# LMD18200_4.net
KiCad netlist of a schematic drawn in EAGLE
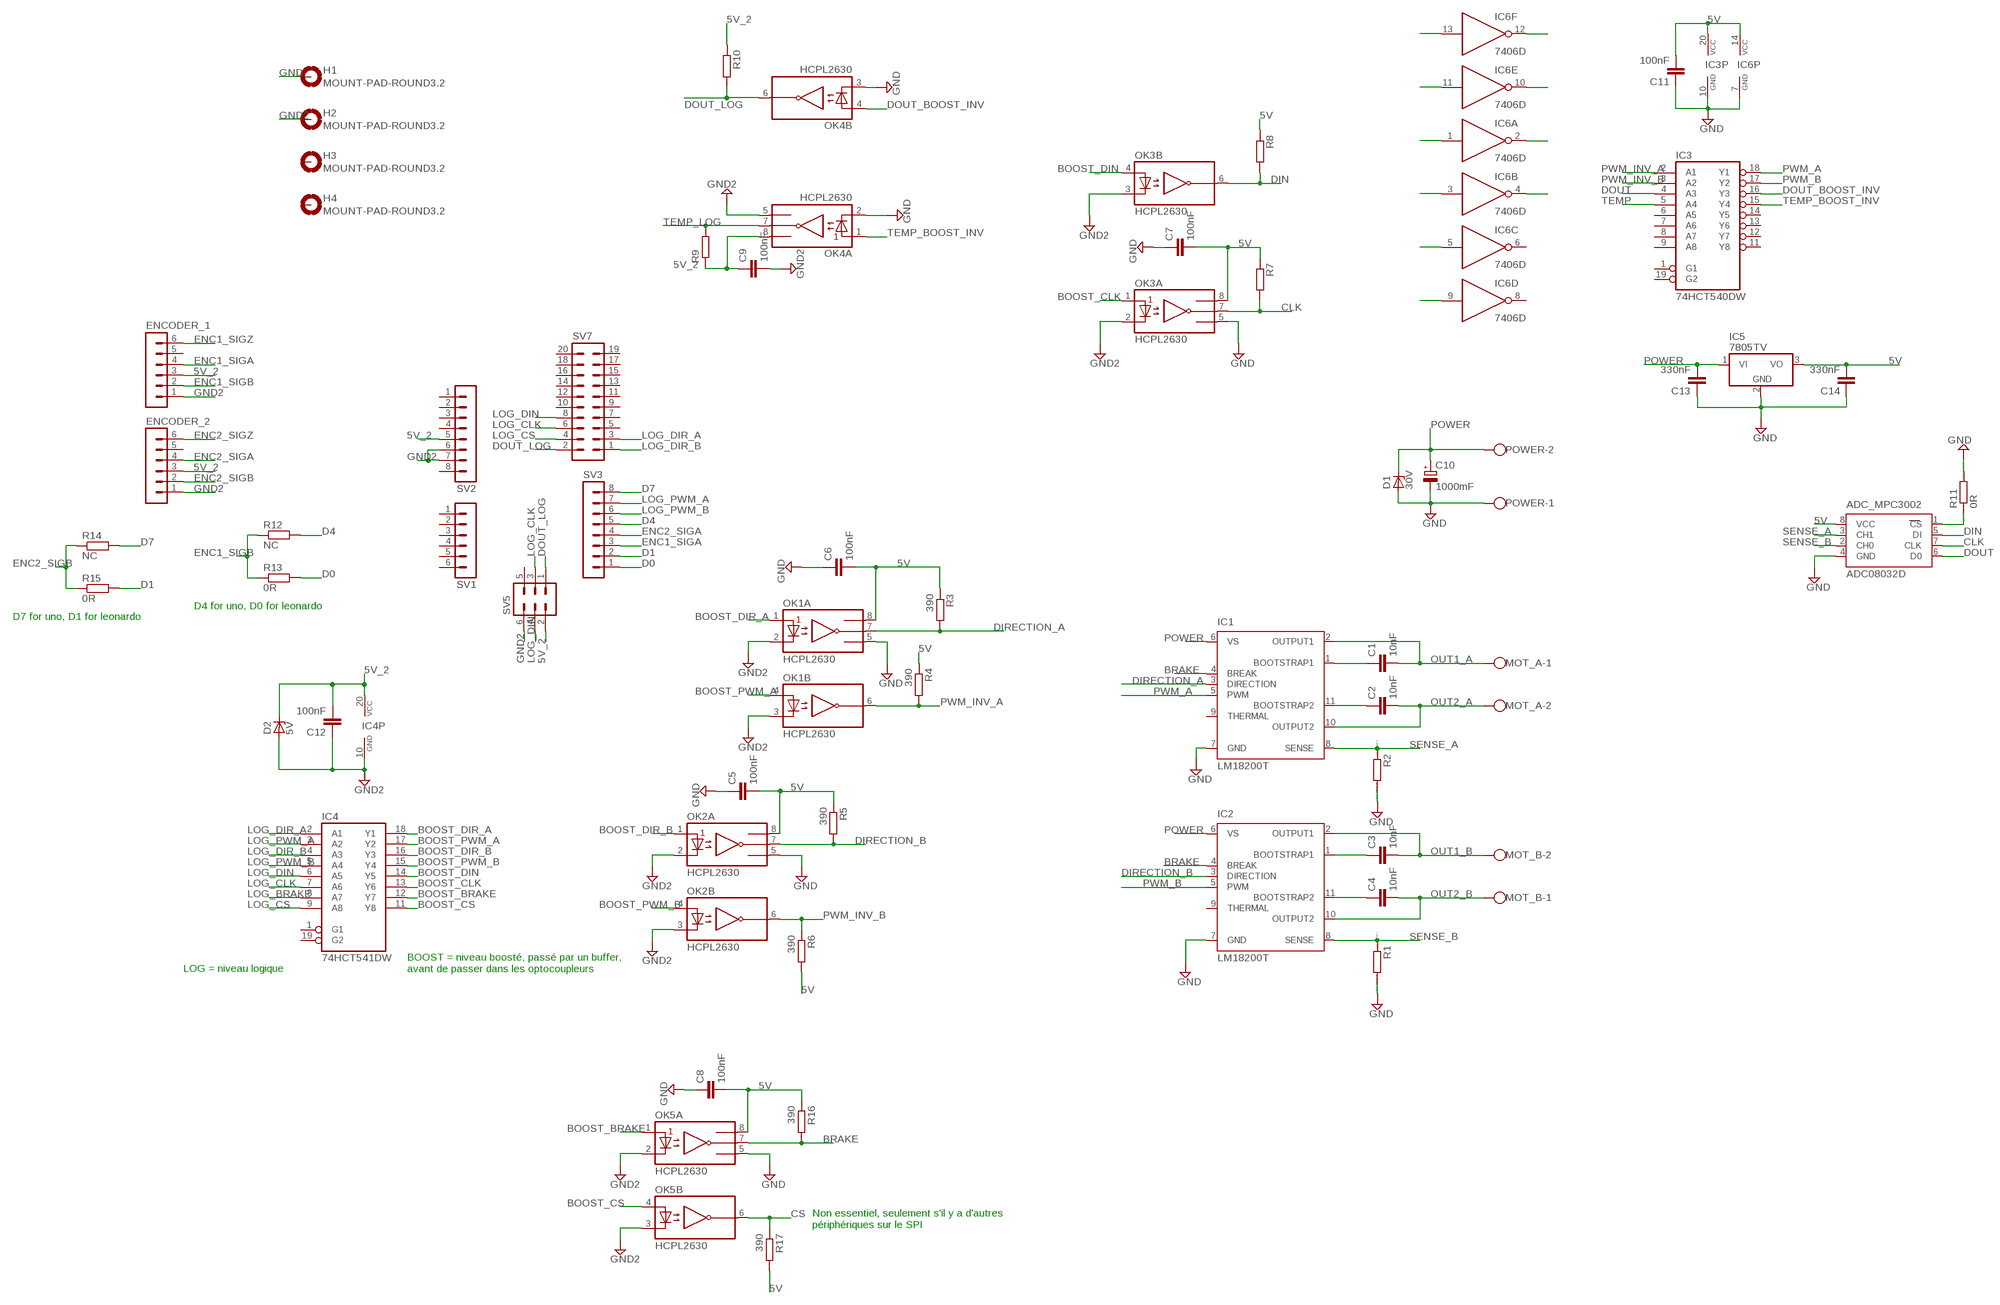
[diagram p0: schematic, sheet 1]

(export (version "E")
  (design (tool "Eeschema 10.0.6"))
  (components
    (comp (ref "ADC_MPC3002")
      (value "ADC08032D")
      (footprint "eagle-import:SO08")
      (libsource (lib "eagle-import") (part "ADC08032D"))
    )
    (comp (ref "C1")
      (value "10nF")
      (footprint "eagle-import:C2.5-2")
      (libsource (lib "eagle-import") (part "C2.5/2"))
    )
    (comp (ref "C2")
      (value "10nF")
      (footprint "eagle-import:C2.5-2")
      (libsource (lib "eagle-import") (part "C2.5/2"))
    )
    (comp (ref "C3")
      (value "10nF")
      (footprint "eagle-import:C2.5-2")
      (libsource (lib "eagle-import") (part "C2.5/2"))
    )
    (comp (ref "C4")
      (value "10nF")
      (footprint "eagle-import:C2.5-2")
      (libsource (lib "eagle-import") (part "C2.5/2"))
    )
    (comp (ref "C5")
      (value "100nF")
      (footprint "eagle-import:C2.5-2")
      (libsource (lib "eagle-import") (part "C2.5/2"))
    )
    (comp (ref "C6")
      (value "100nF")
      (footprint "eagle-import:C2.5-2")
      (libsource (lib "eagle-import") (part "C2.5/2"))
    )
    (comp (ref "C7")
      (value "100nF")
      (footprint "eagle-import:C2.5-2")
      (libsource (lib "eagle-import") (part "C2.5/2"))
    )
    (comp (ref "C8")
      (value "100nF")
      (footprint "eagle-import:C2.5-2")
      (libsource (lib "eagle-import") (part "C2.5/2"))
    )
    (comp (ref "C9")
      (value "100nF")
      (footprint "eagle-import:C2.5-2")
      (libsource (lib "eagle-import") (part "C2.5/2"))
    )
    (comp (ref "C10")
      (value "1000mF")
      (footprint "eagle-import:E7,5-18")
      (libsource (lib "eagle-import") (part "CPOL-EUE7.5-18"))
    )
    (comp (ref "C11")
      (value "100nF")
      (footprint "eagle-import:C2.5-2")
      (libsource (lib "eagle-import") (part "C2.5/2"))
    )
    (comp (ref "C12")
      (value "100nF")
      (footprint "eagle-import:C2.5-2")
      (libsource (lib "eagle-import") (part "C2.5/2"))
    )
    (comp (ref "C13")
      (value "330nF")
      (footprint "eagle-import:C2.5-2")
      (libsource (lib "eagle-import") (part "C2.5/2"))
    )
    (comp (ref "C14")
      (value "330nF")
      (footprint "eagle-import:C2.5-2")
      (libsource (lib "eagle-import") (part "C2.5/2"))
    )
    (comp (ref "D1")
      (value "30V")
      (footprint "eagle-import:SOD80C")
      (libsource (lib "eagle-import") (part "ZENER-DIODESOD80C"))
    )
    (comp (ref "D2")
      (value "5V")
      (footprint "eagle-import:SOD80C")
      (libsource (lib "eagle-import") (part "ZENER-DIODESOD80C"))
    )
    (comp (ref "ENCODER_1")
      (value "MA06-1")
      (footprint "eagle-import:MA06-1")
      (libsource (lib "eagle-import") (part "MA06-1"))
    )
    (comp (ref "ENCODER_2")
      (value "MA06-1")
      (footprint "eagle-import:MA06-1")
      (libsource (lib "eagle-import") (part "MA06-1"))
    )
    (comp (ref "H1")
      (value "MOUNT-PAD-ROUND3.2")
      (footprint "eagle-import:3,2-PAD")
      (libsource (lib "eagle-import") (part "MOUNT-PAD-ROUND3.2"))
    )
    (comp (ref "H2")
      (value "MOUNT-PAD-ROUND3.2")
      (footprint "eagle-import:3,2-PAD")
      (libsource (lib "eagle-import") (part "MOUNT-PAD-ROUND3.2"))
    )
    (comp (ref "H3")
      (value "MOUNT-PAD-ROUND3.2")
      (footprint "eagle-import:3,2-PAD")
      (libsource (lib "eagle-import") (part "MOUNT-PAD-ROUND3.2"))
    )
    (comp (ref "H4")
      (value "MOUNT-PAD-ROUND3.2")
      (footprint "eagle-import:3,2-PAD")
      (libsource (lib "eagle-import") (part "MOUNT-PAD-ROUND3.2"))
    )
    (comp (ref "IC1")
      (value "LM18200T")
      (footprint "eagle-import:TO-220-11")
      (libsource (lib "eagle-import") (part "LM18200T"))
    )
    (comp (ref "IC2")
      (value "LM18200T")
      (footprint "eagle-import:TO-220-11")
      (libsource (lib "eagle-import") (part "LM18200T"))
    )
    (comp (ref "IC3")
      (value "74HCT540DW")
      (footprint "eagle-import:SO20W")
      (libsource (lib "eagle-import") (part "74540DWHCT"))
    )
    (comp (ref "IC4")
      (value "74HCT541DW")
      (footprint "eagle-import:SO20W")
      (libsource (lib "eagle-import") (part "74541DWHCT"))
    )
    (comp (ref "IC5")
      (value "7805TV")
      (footprint "eagle-import:TO220V")
      (libsource (lib "eagle-import") (part "78TV05"))
    )
    (comp (ref "IC6")
      (value "7406D")
      (footprint "eagle-import:SO14")
      (libsource (lib "eagle-import") (part "7406D"))
    )
    (comp (ref "MOT_A")
      (value "W237-102")
      (footprint "eagle-import:W237-102")
      (fields (field (name "MPN") "237-102"))
      (libsource (lib "eagle-import") (part "W237-102"))
    )
    (comp (ref "MOT_B")
      (value "W237-102")
      (footprint "eagle-import:W237-102")
      (fields (field (name "MPN") "237-102"))
      (libsource (lib "eagle-import") (part "W237-102"))
    )
    (comp (ref "OK1")
      (value "HCPL2630")
      (footprint "eagle-import:DIL08")
      (fields (field (name "MF") "AGILENT TECHNOLOGIES") (field (name "MPN") "HCPL-2630-000E"))
      (libsource (lib "eagle-import") (part "HCPL2630"))
    )
    (comp (ref "OK2")
      (value "HCPL2630")
      (footprint "eagle-import:DIL08")
      (fields (field (name "MF") "AGILENT TECHNOLOGIES") (field (name "MPN") "HCPL-2630-000E"))
      (libsource (lib "eagle-import") (part "HCPL2630"))
    )
    (comp (ref "OK3")
      (value "HCPL2630")
      (footprint "eagle-import:DIL08")
      (fields (field (name "MF") "AGILENT TECHNOLOGIES") (field (name "MPN") "HCPL-2630-000E"))
      (libsource (lib "eagle-import") (part "HCPL2630"))
    )
    (comp (ref "OK4")
      (value "HCPL2630")
      (footprint "eagle-import:DIL08")
      (fields (field (name "MF") "AGILENT TECHNOLOGIES") (field (name "MPN") "HCPL-2630-000E"))
      (libsource (lib "eagle-import") (part "HCPL2630"))
    )
    (comp (ref "OK5")
      (value "HCPL2630")
      (footprint "eagle-import:DIL08")
      (fields (field (name "MF") "AGILENT TECHNOLOGIES") (field (name "MPN") "HCPL-2630-000E"))
      (libsource (lib "eagle-import") (part "HCPL2630"))
    )
    (comp (ref "POWER")
      (value "W237-102")
      (footprint "eagle-import:W237-102")
      (fields (field (name "MPN") "237-102"))
      (libsource (lib "eagle-import") (part "W237-102"))
    )
    (comp (ref "R1") (value "R") (footprint "eagle-import:R0805") (libsource (lib "eagle-import") (part "R")))
    (comp (ref "R2") (value "R") (footprint "eagle-import:R0805") (libsource (lib "eagle-import") (part "R")))
    (comp (ref "R3")
      (value "390")
      (footprint "eagle-import:R0805")
      (libsource (lib "eagle-import") (part "R-EU_R0805"))
    )
    (comp (ref "R4")
      (value "390")
      (footprint "eagle-import:R0805")
      (libsource (lib "eagle-import") (part "R-EU_R0805"))
    )
    (comp (ref "R5")
      (value "390")
      (footprint "eagle-import:R0805")
      (libsource (lib "eagle-import") (part "R-EU_R0805"))
    )
    (comp (ref "R6")
      (value "390")
      (footprint "eagle-import:R0805")
      (libsource (lib "eagle-import") (part "R-EU_R0805"))
    )
    (comp (ref "R7")
      (value "R-EU_R0805")
      (footprint "eagle-import:R0805")
      (libsource (lib "eagle-import") (part "R-EU_R0805"))
    )
    (comp (ref "R8")
      (value "R-EU_R0805")
      (footprint "eagle-import:R0805")
      (libsource (lib "eagle-import") (part "R-EU_R0805"))
    )
    (comp (ref "R9")
      (value "R-EU_R0805")
      (footprint "eagle-import:R0805")
      (libsource (lib "eagle-import") (part "R-EU_R0805"))
    )
    (comp (ref "R10")
      (value "R-EU_R0805")
      (footprint "eagle-import:R0805")
      (libsource (lib "eagle-import") (part "R-EU_R0805"))
    )
    (comp (ref "R11")
      (value "0R")
      (footprint "eagle-import:R0805")
      (libsource (lib "eagle-import") (part "R"))
    )
    (comp (ref "R12")
      (value "NC")
      (footprint "eagle-import:R0805")
      (libsource (lib "eagle-import") (part "R-EU_R0805"))
    )
    (comp (ref "R13")
      (value "0R")
      (footprint "eagle-import:R0805")
      (libsource (lib "eagle-import") (part "R-EU_R0805"))
    )
    (comp (ref "R14")
      (value "NC")
      (footprint "eagle-import:R0805")
      (libsource (lib "eagle-import") (part "R-EU_R0805"))
    )
    (comp (ref "R15")
      (value "0R")
      (footprint "eagle-import:R0805")
      (libsource (lib "eagle-import") (part "R-EU_R0805"))
    )
    (comp (ref "R16")
      (value "390")
      (footprint "eagle-import:R0805")
      (libsource (lib "eagle-import") (part "R-EU_R0805"))
    )
    (comp (ref "R17")
      (value "390")
      (footprint "eagle-import:R0805")
      (libsource (lib "eagle-import") (part "R-EU_R0805"))
    )
    (comp (ref "SV1")
      (value "MA06-1")
      (footprint "eagle-import:MA06-1")
      (libsource (lib "eagle-import") (part "MA06-1"))
    )
    (comp (ref "SV2")
      (value "MA08-1")
      (footprint "eagle-import:MA08-1")
      (libsource (lib "eagle-import") (part "MA08-1"))
    )
    (comp (ref "SV3")
      (value "MA08-1")
      (footprint "eagle-import:MA08-1")
      (libsource (lib "eagle-import") (part "MA08-1"))
    )
    (comp (ref "SV5")
      (value "MA03-2")
      (footprint "eagle-import:MA03-2")
      (libsource (lib "eagle-import") (part "MA03-2"))
    )
    (comp (ref "SV7")
      (value "MA10-2")
      (footprint "eagle-import:MA10-2")
      (libsource (lib "eagle-import") (part "MA10-2"))
    )
  )
  (nets
    (net (code "1") (name "/5V") (class "Default")
      (node (ref "ADC_MPC3002") (pin "8") (pinfunction "VCC_8") (pintype "power_in"))
      (node (ref "C11") (pin "2") (pinfunction "2_2") (pintype "passive"))
      (node (ref "C14") (pin "2") (pinfunction "2_2") (pintype "passive"))
      (node (ref "C5") (pin "2") (pinfunction "2_2") (pintype "passive"))
      (node (ref "C6") (pin "2") (pinfunction "2_2") (pintype "passive"))
      (node (ref "C7") (pin "2") (pinfunction "2_2") (pintype "passive"))
      (node (ref "C8") (pin "2") (pinfunction "2_2") (pintype "passive"))
      (node (ref "IC3") (pin "20") (pinfunction "VCC_20") (pintype "power_in"))
      (node (ref "IC5") (pin "3") (pinfunction "VO_3") (pintype "passive"))
      (node (ref "IC6") (pin "14") (pinfunction "VCC_14") (pintype "power_in"))
      (node (ref "OK1") (pin "8") (pinfunction "VCC_8") (pintype "passive"))
      (node (ref "OK2") (pin "8") (pinfunction "VCC_8") (pintype "passive"))
      (node (ref "OK3") (pin "8") (pinfunction "VCC_8") (pintype "passive"))
      (node (ref "OK5") (pin "8") (pinfunction "VCC_8") (pintype "passive"))
      (node (ref "R16") (pin "1") (pinfunction "1_1") (pintype "passive"))
      (node (ref "R17") (pin "2") (pinfunction "2_2") (pintype "passive"))
      (node (ref "R3") (pin "1") (pinfunction "1_1") (pintype "passive"))
      (node (ref "R4") (pin "1") (pinfunction "1_1") (pintype "passive"))
      (node (ref "R5") (pin "1") (pinfunction "1_1") (pintype "passive"))
      (node (ref "R6") (pin "2") (pinfunction "2_2") (pintype "passive"))
      (node (ref "R7") (pin "1") (pinfunction "1_1") (pintype "passive"))
      (node (ref "R8") (pin "1") (pinfunction "1_1") (pintype "passive"))
    )
    (net (code "2") (name "/5V_2") (class "Default")
      (node (ref "C12") (pin "2") (pinfunction "2_2") (pintype "passive"))
      (node (ref "C9") (pin "1") (pinfunction "1_1") (pintype "passive"))
      (node (ref "D2") (pin "C") (pinfunction "C_C") (pintype "passive"))
      (node (ref "ENCODER_1") (pin "3") (pinfunction "3_3") (pintype "passive"))
      (node (ref "ENCODER_2") (pin "3") (pinfunction "3_3") (pintype "passive"))
      (node (ref "IC4") (pin "20") (pinfunction "VCC_20") (pintype "power_in"))
      (node (ref "OK4") (pin "8") (pinfunction "VCC_8") (pintype "passive"))
      (node (ref "R10") (pin "1") (pinfunction "1_1") (pintype "passive"))
      (node (ref "R9") (pin "1") (pinfunction "1_1") (pintype "passive"))
      (node (ref "SV2") (pin "5") (pinfunction "5_5") (pintype "passive"))
      (node (ref "SV5") (pin "2") (pinfunction "2_2") (pintype "passive"))
    )
    (net (code "3") (name "/BOOST_BRAKE") (class "Default")
      (node (ref "IC4") (pin "12") (pinfunction "Y7_12") (pintype "tri_state"))
      (node (ref "OK5") (pin "1") (pinfunction "A1_1") (pintype "passive"))
    )
    (net (code "4") (name "/BOOST_CLK") (class "Default")
      (node (ref "IC4") (pin "13") (pinfunction "Y6_13") (pintype "tri_state"))
      (node (ref "OK3") (pin "1") (pinfunction "A1_1") (pintype "passive"))
    )
    (net (code "5") (name "/BOOST_CS") (class "Default")
      (node (ref "IC4") (pin "11") (pinfunction "Y8_11") (pintype "tri_state"))
      (node (ref "OK5") (pin "4") (pinfunction "A2_4") (pintype "passive"))
    )
    (net (code "6") (name "/BOOST_DIN") (class "Default")
      (node (ref "IC4") (pin "14") (pinfunction "Y5_14") (pintype "tri_state"))
      (node (ref "OK3") (pin "4") (pinfunction "A2_4") (pintype "passive"))
    )
    (net (code "7") (name "/BOOST_DIR_A") (class "Default")
      (node (ref "IC4") (pin "18") (pinfunction "Y1_18") (pintype "tri_state"))
      (node (ref "OK1") (pin "1") (pinfunction "A1_1") (pintype "passive"))
    )
    (net (code "8") (name "/BOOST_DIR_B") (class "Default")
      (node (ref "IC4") (pin "16") (pinfunction "Y3_16") (pintype "tri_state"))
      (node (ref "OK2") (pin "1") (pinfunction "A1_1") (pintype "passive"))
    )
    (net (code "9") (name "/BOOST_PWM_A") (class "Default")
      (node (ref "IC4") (pin "17") (pinfunction "Y2_17") (pintype "tri_state"))
      (node (ref "OK1") (pin "4") (pinfunction "A2_4") (pintype "passive"))
    )
    (net (code "10") (name "/BOOST_PWM_B") (class "Default")
      (node (ref "IC4") (pin "15") (pinfunction "Y4_15") (pintype "tri_state"))
      (node (ref "OK2") (pin "4") (pinfunction "A2_4") (pintype "passive"))
    )
    (net (code "11") (name "/BRAKE") (class "Default")
      (node (ref "IC1") (pin "4") (pinfunction "BREAK_4") (pintype "input"))
      (node (ref "IC2") (pin "4") (pinfunction "BREAK_4") (pintype "input"))
      (node (ref "OK5") (pin "7") (pinfunction "VO1_7") (pintype "passive"))
      (node (ref "R16") (pin "2") (pinfunction "2_2") (pintype "passive"))
    )
    (net (code "12") (name "/CLK") (class "Default")
      (node (ref "ADC_MPC3002") (pin "7") (pinfunction "CLK_7") (pintype "input"))
      (node (ref "OK3") (pin "7") (pinfunction "VO1_7") (pintype "passive"))
      (node (ref "R7") (pin "2") (pinfunction "2_2") (pintype "passive"))
    )
    (net (code "13") (name "/CS") (class "Default")
      (node (ref "ADC_MPC3002") (pin "1") (pinfunction "CS_1") (pintype "input"))
      (node (ref "OK5") (pin "6") (pinfunction "VO2_6") (pintype "passive"))
      (node (ref "R11") (pin "1") (pinfunction "1_1") (pintype "passive"))
      (node (ref "R17") (pin "1") (pinfunction "1_1") (pintype "passive"))
    )
    (net (code "14") (name "/D0") (class "Default")
      (node (ref "R13") (pin "2") (pinfunction "2_2") (pintype "passive"))
      (node (ref "SV3") (pin "1") (pinfunction "1_1") (pintype "passive"))
    )
    (net (code "15") (name "/D1") (class "Default")
      (node (ref "R15") (pin "2") (pinfunction "2_2") (pintype "passive"))
      (node (ref "SV3") (pin "2") (pinfunction "2_2") (pintype "passive"))
    )
    (net (code "16") (name "/D4") (class "Default")
      (node (ref "R12") (pin "2") (pinfunction "2_2") (pintype "passive"))
      (node (ref "SV3") (pin "5") (pinfunction "5_5") (pintype "passive"))
    )
    (net (code "17") (name "/D7") (class "Default")
      (node (ref "R14") (pin "2") (pinfunction "2_2") (pintype "passive"))
      (node (ref "SV3") (pin "8") (pinfunction "8_8") (pintype "passive"))
    )
    (net (code "18") (name "/DIN") (class "Default")
      (node (ref "ADC_MPC3002") (pin "5") (pinfunction "DI_5") (pintype "input"))
      (node (ref "OK3") (pin "6") (pinfunction "VO2_6") (pintype "passive"))
      (node (ref "R8") (pin "2") (pinfunction "2_2") (pintype "passive"))
    )
    (net (code "19") (name "/DIRECTION_A") (class "Default")
      (node (ref "IC1") (pin "3") (pinfunction "DIRECTION_3") (pintype "input"))
      (node (ref "OK1") (pin "7") (pinfunction "VO1_7") (pintype "passive"))
      (node (ref "R3") (pin "2") (pinfunction "2_2") (pintype "passive"))
    )
    (net (code "20") (name "/DIRECTION_B") (class "Default")
      (node (ref "IC2") (pin "3") (pinfunction "DIRECTION_3") (pintype "input"))
      (node (ref "OK2") (pin "7") (pinfunction "VO1_7") (pintype "passive"))
      (node (ref "R5") (pin "2") (pinfunction "2_2") (pintype "passive"))
    )
    (net (code "21") (name "/DOUT") (class "Default")
      (node (ref "ADC_MPC3002") (pin "6") (pinfunction "D0_6") (pintype "tri_state"))
      (node (ref "IC3") (pin "4") (pinfunction "A3_4") (pintype "input"))
    )
    (net (code "22") (name "/DOUT_BOOST_INV") (class "Default")
      (node (ref "IC3") (pin "16") (pinfunction "Y3_16") (pintype "tri_state"))
      (node (ref "OK4") (pin "4") (pinfunction "A2_4") (pintype "passive"))
    )
    (net (code "23") (name "/DOUT_LOG") (class "Default")
      (node (ref "OK4") (pin "6") (pinfunction "VO2_6") (pintype "passive"))
      (node (ref "R10") (pin "2") (pinfunction "2_2") (pintype "passive"))
      (node (ref "SV5") (pin "1") (pinfunction "1_1") (pintype "passive"))
      (node (ref "SV7") (pin "2") (pinfunction "2_2") (pintype "passive"))
    )
    (net (code "24") (name "/ENC1_SIGA") (class "Default")
      (node (ref "ENCODER_1") (pin "4") (pinfunction "4_4") (pintype "passive"))
      (node (ref "SV3") (pin "3") (pinfunction "3_3") (pintype "passive"))
    )
    (net (code "25") (name "/ENC1_SIGB") (class "Default")
      (node (ref "ENCODER_1") (pin "2") (pinfunction "2_2") (pintype "passive"))
      (node (ref "R12") (pin "1") (pinfunction "1_1") (pintype "passive"))
      (node (ref "R13") (pin "1") (pinfunction "1_1") (pintype "passive"))
    )
    (net (code "26") (name "/ENC1_SIGZ") (class "Default")
      (node (ref "ENCODER_1") (pin "6") (pinfunction "6_6") (pintype "passive"))
    )
    (net (code "27") (name "/ENC2_SIGA") (class "Default")
      (node (ref "ENCODER_2") (pin "4") (pinfunction "4_4") (pintype "passive"))
      (node (ref "SV3") (pin "4") (pinfunction "4_4") (pintype "passive"))
    )
    (net (code "28") (name "/ENC2_SIGB") (class "Default")
      (node (ref "ENCODER_2") (pin "2") (pinfunction "2_2") (pintype "passive"))
      (node (ref "R14") (pin "1") (pinfunction "1_1") (pintype "passive"))
      (node (ref "R15") (pin "1") (pinfunction "1_1") (pintype "passive"))
    )
    (net (code "29") (name "/ENC2_SIGZ") (class "Default")
      (node (ref "ENCODER_2") (pin "6") (pinfunction "6_6") (pintype "passive"))
    )
    (net (code "30") (name "/LOG_BRAKE") (class "Default")
      (node (ref "IC4") (pin "8") (pinfunction "A7_8") (pintype "input"))
    )
    (net (code "31") (name "/LOG_CLK") (class "Default")
      (node (ref "IC4") (pin "7") (pinfunction "A6_7") (pintype "input"))
      (node (ref "SV5") (pin "3") (pinfunction "3_3") (pintype "passive"))
      (node (ref "SV7") (pin "6") (pinfunction "6_6") (pintype "passive"))
    )
    (net (code "32") (name "/LOG_CS") (class "Default")
      (node (ref "IC4") (pin "9") (pinfunction "A8_9") (pintype "input"))
      (node (ref "SV7") (pin "4") (pinfunction "4_4") (pintype "passive"))
    )
    (net (code "33") (name "/LOG_DIN") (class "Default")
      (node (ref "IC4") (pin "6") (pinfunction "A5_6") (pintype "input"))
      (node (ref "SV5") (pin "4") (pinfunction "4_4") (pintype "passive"))
      (node (ref "SV7") (pin "8") (pinfunction "8_8") (pintype "passive"))
    )
    (net (code "34") (name "/LOG_DIR_A") (class "Default")
      (node (ref "IC4") (pin "2") (pinfunction "A1_2") (pintype "input"))
      (node (ref "SV7") (pin "3") (pinfunction "3_3") (pintype "passive"))
    )
    (net (code "35") (name "/LOG_DIR_B") (class "Default")
      (node (ref "IC4") (pin "4") (pinfunction "A3_4") (pintype "input"))
      (node (ref "SV7") (pin "1") (pinfunction "1_1") (pintype "passive"))
    )
    (net (code "36") (name "/LOG_PWM_A") (class "Default")
      (node (ref "IC4") (pin "3") (pinfunction "A2_3") (pintype "input"))
      (node (ref "SV3") (pin "7") (pinfunction "7_7") (pintype "passive"))
    )
    (net (code "37") (name "/LOG_PWM_B") (class "Default")
      (node (ref "IC4") (pin "5") (pinfunction "A4_5") (pintype "input"))
      (node (ref "SV3") (pin "6") (pinfunction "6_6") (pintype "passive"))
    )
    (net (code "38") (name "/OUT1_A") (class "Default")
      (node (ref "C1") (pin "2") (pinfunction "2_2") (pintype "passive"))
      (node (ref "IC1") (pin "2") (pinfunction "OUTPUT1_2") (pintype "output"))
      (node (ref "MOT_A") (pin "1") (pinfunction "KL_1") (pintype "passive"))
    )
    (net (code "39") (name "/OUT1_B") (class "Default")
      (node (ref "C3") (pin "2") (pinfunction "2_2") (pintype "passive"))
      (node (ref "IC2") (pin "2") (pinfunction "OUTPUT1_2") (pintype "output"))
      (node (ref "MOT_B") (pin "2") (pinfunction "KL_2") (pintype "passive"))
    )
    (net (code "40") (name "/OUT2_A") (class "Default")
      (node (ref "C2") (pin "2") (pinfunction "2_2") (pintype "passive"))
      (node (ref "IC1") (pin "10") (pinfunction "OUTPUT2_10") (pintype "output"))
      (node (ref "MOT_A") (pin "2") (pinfunction "KL_2") (pintype "passive"))
    )
    (net (code "41") (name "/OUT2_B") (class "Default")
      (node (ref "C4") (pin "2") (pinfunction "2_2") (pintype "passive"))
      (node (ref "IC2") (pin "10") (pinfunction "OUTPUT2_10") (pintype "output"))
      (node (ref "MOT_B") (pin "1") (pinfunction "KL_1") (pintype "passive"))
    )
    (net (code "42") (name "/POWER") (class "Default")
      (node (ref "C10") (pin "+") (pinfunction "+_+") (pintype "passive"))
      (node (ref "C13") (pin "2") (pinfunction "2_2") (pintype "passive"))
      (node (ref "D1") (pin "C") (pinfunction "C_C") (pintype "passive"))
      (node (ref "IC1") (pin "6") (pinfunction "VS_6") (pintype "power_in"))
      (node (ref "IC2") (pin "6") (pinfunction "VS_6") (pintype "power_in"))
      (node (ref "IC5") (pin "1") (pinfunction "VI_1") (pintype "input"))
      (node (ref "POWER") (pin "2") (pinfunction "KL_2") (pintype "passive"))
    )
    (net (code "43") (name "/PWM_A") (class "Default")
      (node (ref "IC1") (pin "5") (pinfunction "PWM_5") (pintype "input"))
      (node (ref "IC3") (pin "18") (pinfunction "Y1_18") (pintype "tri_state"))
    )
    (net (code "44") (name "/PWM_B") (class "Default")
      (node (ref "IC2") (pin "5") (pinfunction "PWM_5") (pintype "input"))
      (node (ref "IC3") (pin "17") (pinfunction "Y2_17") (pintype "tri_state"))
    )
    (net (code "45") (name "/PWM_INV_A") (class "Default")
      (node (ref "IC3") (pin "2") (pinfunction "A1_2") (pintype "input"))
      (node (ref "OK1") (pin "6") (pinfunction "VO2_6") (pintype "passive"))
      (node (ref "R4") (pin "2") (pinfunction "2_2") (pintype "passive"))
    )
    (net (code "46") (name "/PWM_INV_B") (class "Default")
      (node (ref "IC3") (pin "3") (pinfunction "A2_3") (pintype "input"))
      (node (ref "OK2") (pin "6") (pinfunction "VO2_6") (pintype "passive"))
      (node (ref "R6") (pin "1") (pinfunction "1_1") (pintype "passive"))
    )
    (net (code "47") (name "/SENSE_A") (class "Default")
      (node (ref "ADC_MPC3002") (pin "3") (pinfunction "CH1_3") (pintype "input"))
      (node (ref "IC1") (pin "8") (pinfunction "SENSE_8") (pintype "output"))
      (node (ref "R2") (pin "1") (pinfunction "1_1") (pintype "passive"))
    )
    (net (code "48") (name "/SENSE_B") (class "Default")
      (node (ref "ADC_MPC3002") (pin "2") (pinfunction "CH0_2") (pintype "input"))
      (node (ref "IC2") (pin "8") (pinfunction "SENSE_8") (pintype "output"))
      (node (ref "R1") (pin "1") (pinfunction "1_1") (pintype "passive"))
    )
    (net (code "49") (name "/TEMP") (class "Default")
      (node (ref "IC3") (pin "5") (pinfunction "A4_5") (pintype "input"))
    )
    (net (code "50") (name "/TEMP_BOOST_INV") (class "Default")
      (node (ref "IC3") (pin "15") (pinfunction "Y4_15") (pintype "tri_state"))
      (node (ref "OK4") (pin "1") (pinfunction "A1_1") (pintype "passive"))
    )
    (net (code "51") (name "/TEMP_LOG") (class "Default")
      (node (ref "OK4") (pin "7") (pinfunction "VO1_7") (pintype "passive"))
      (node (ref "R9") (pin "2") (pinfunction "2_2") (pintype "passive"))
    )
    (net (code "52") (name "GND") (class "Default")
      (node (ref "ADC_MPC3002") (pin "4") (pinfunction "GND_4") (pintype "power_in"))
      (node (ref "C10") (pin "-") (pinfunction "-_-") (pintype "passive"))
      (node (ref "C11") (pin "1") (pinfunction "1_1") (pintype "passive"))
      (node (ref "C13") (pin "1") (pinfunction "1_1") (pintype "passive"))
      (node (ref "C14") (pin "1") (pinfunction "1_1") (pintype "passive"))
      (node (ref "C5") (pin "1") (pinfunction "1_1") (pintype "passive"))
      (node (ref "C6") (pin "1") (pinfunction "1_1") (pintype "passive"))
      (node (ref "C7") (pin "1") (pinfunction "1_1") (pintype "passive"))
      (node (ref "C8") (pin "1") (pinfunction "1_1") (pintype "passive"))
      (node (ref "D1") (pin "A") (pinfunction "A_A") (pintype "passive"))
      (node (ref "H1") (pin "B3,2") (pinfunction "MOUNT_B3,2") (pintype "passive"))
      (node (ref "IC1") (pin "7") (pinfunction "GND_7") (pintype "power_in"))
      (node (ref "IC2") (pin "7") (pinfunction "GND_7") (pintype "power_in"))
      (node (ref "IC3") (pin "10") (pinfunction "GND_10") (pintype "power_in"))
      (node (ref "IC5") (pin "2") (pinfunction "GND_2") (pintype "passive"))
      (node (ref "IC6") (pin "7") (pinfunction "GND_7") (pintype "power_in"))
      (node (ref "OK1") (pin "5") (pinfunction "GND_5") (pintype "passive"))
      (node (ref "OK2") (pin "5") (pinfunction "GND_5") (pintype "passive"))
      (node (ref "OK3") (pin "5") (pinfunction "GND_5") (pintype "passive"))
      (node (ref "OK4") (pin "2") (pinfunction "C1_2") (pintype "passive"))
      (node (ref "OK4") (pin "3") (pinfunction "C2_3") (pintype "passive"))
      (node (ref "OK5") (pin "5") (pinfunction "GND_5") (pintype "passive"))
      (node (ref "POWER") (pin "1") (pinfunction "KL_1") (pintype "passive"))
      (node (ref "R1") (pin "2") (pinfunction "2_2") (pintype "passive"))
      (node (ref "R11") (pin "2") (pinfunction "2_2") (pintype "passive"))
      (node (ref "R2") (pin "2") (pinfunction "2_2") (pintype "passive"))
    )
    (net (code "53") (name "GND2") (class "Default")
      (node (ref "C12") (pin "1") (pinfunction "1_1") (pintype "passive"))
      (node (ref "C9") (pin "2") (pinfunction "2_2") (pintype "passive"))
      (node (ref "D2") (pin "A") (pinfunction "A_A") (pintype "passive"))
      (node (ref "ENCODER_1") (pin "1") (pinfunction "1_1") (pintype "passive"))
      (node (ref "ENCODER_2") (pin "1") (pinfunction "1_1") (pintype "passive"))
      (node (ref "H2") (pin "B3,2") (pinfunction "MOUNT_B3,2") (pintype "passive"))
      (node (ref "IC4") (pin "10") (pinfunction "GND_10") (pintype "power_in"))
      (node (ref "OK1") (pin "2") (pinfunction "C1_2") (pintype "passive"))
      (node (ref "OK1") (pin "3") (pinfunction "C2_3") (pintype "passive"))
      (node (ref "OK2") (pin "2") (pinfunction "C1_2") (pintype "passive"))
      (node (ref "OK2") (pin "3") (pinfunction "C2_3") (pintype "passive"))
      (node (ref "OK3") (pin "2") (pinfunction "C1_2") (pintype "passive"))
      (node (ref "OK3") (pin "3") (pinfunction "C2_3") (pintype "passive"))
      (node (ref "OK4") (pin "5") (pinfunction "GND_5") (pintype "passive"))
      (node (ref "OK5") (pin "2") (pinfunction "C1_2") (pintype "passive"))
      (node (ref "OK5") (pin "3") (pinfunction "C2_3") (pintype "passive"))
      (node (ref "SV2") (pin "6") (pinfunction "6_6") (pintype "passive"))
      (node (ref "SV2") (pin "7") (pinfunction "7_7") (pintype "passive"))
      (node (ref "SV5") (pin "6") (pinfunction "6_6") (pintype "passive"))
    )
    (net (code "54") (name "Net-(IC1-BOOTSTRAP1)") (class "Default")
      (node (ref "C1") (pin "1") (pinfunction "1_1") (pintype "passive"))
      (node (ref "IC1") (pin "1") (pinfunction "BOOTSTRAP1_1") (pintype "input"))
    )
    (net (code "55") (name "Net-(IC1-BOOTSTRAP2)") (class "Default")
      (node (ref "C2") (pin "1") (pinfunction "1_1") (pintype "passive"))
      (node (ref "IC1") (pin "11") (pinfunction "BOOTSTRAP2_11") (pintype "input"))
    )
    (net (code "56") (name "Net-(IC2-BOOTSTRAP1)") (class "Default")
      (node (ref "C3") (pin "1") (pinfunction "1_1") (pintype "passive"))
      (node (ref "IC2") (pin "1") (pinfunction "BOOTSTRAP1_1") (pintype "input"))
    )
    (net (code "57") (name "Net-(IC2-BOOTSTRAP2)") (class "Default")
      (node (ref "C4") (pin "1") (pinfunction "1_1") (pintype "passive"))
      (node (ref "IC2") (pin "11") (pinfunction "BOOTSTRAP2_11") (pintype "input"))
    )
    (net (code "58") (name "unconnected-(ENCODER_1-Pad5)") (class "Default")
      (node (ref "ENCODER_1") (pin "5") (pinfunction "5_5") (pintype "passive"))
    )
    (net (code "59") (name "unconnected-(ENCODER_2-Pad5)") (class "Default")
      (node (ref "ENCODER_2") (pin "5") (pinfunction "5_5") (pintype "passive"))
    )
    (net (code "60") (name "unconnected-(H3-MOUNT-PadB3,2)") (class "Default")
      (node (ref "H3") (pin "B3,2") (pinfunction "MOUNT_B3,2") (pintype "passive"))
    )
    (net (code "61") (name "unconnected-(H4-MOUNT-PadB3,2)") (class "Default")
      (node (ref "H4") (pin "B3,2") (pinfunction "MOUNT_B3,2") (pintype "passive"))
    )
    (net (code "62") (name "unconnected-(IC1-THERMAL-Pad9)") (class "Default")
      (node (ref "IC1") (pin "9") (pinfunction "THERMAL_9") (pintype "output"))
    )
    (net (code "63") (name "unconnected-(IC2-THERMAL-Pad9)") (class "Default")
      (node (ref "IC2") (pin "9") (pinfunction "THERMAL_9") (pintype "output"))
    )
    (net (code "64") (name "unconnected-(IC3A-A5-Pad6)") (class "Default")
      (node (ref "IC3") (pin "6") (pinfunction "A5_6") (pintype "input"))
    )
    (net (code "65") (name "unconnected-(IC3A-A6-Pad7)") (class "Default")
      (node (ref "IC3") (pin "7") (pinfunction "A6_7") (pintype "input"))
    )
    (net (code "66") (name "unconnected-(IC3A-A7-Pad8)") (class "Default")
      (node (ref "IC3") (pin "8") (pinfunction "A7_8") (pintype "input"))
    )
    (net (code "67") (name "unconnected-(IC3A-A8-Pad9)") (class "Default")
      (node (ref "IC3") (pin "9") (pinfunction "A8_9") (pintype "input"))
    )
    (net (code "68") (name "unconnected-(IC3A-G1-Pad1)") (class "Default")
      (node (ref "IC3") (pin "1") (pinfunction "G1_1") (pintype "input"))
    )
    (net (code "69") (name "unconnected-(IC3A-G2-Pad19)") (class "Default")
      (node (ref "IC3") (pin "19") (pinfunction "G2_19") (pintype "input"))
    )
    (net (code "70") (name "unconnected-(IC3A-Y5-Pad14)") (class "Default")
      (node (ref "IC3") (pin "14") (pinfunction "Y5_14") (pintype "tri_state"))
    )
    (net (code "71") (name "unconnected-(IC3A-Y6-Pad13)") (class "Default")
      (node (ref "IC3") (pin "13") (pinfunction "Y6_13") (pintype "tri_state"))
    )
    (net (code "72") (name "unconnected-(IC3A-Y7-Pad12)") (class "Default")
      (node (ref "IC3") (pin "12") (pinfunction "Y7_12") (pintype "tri_state"))
    )
    (net (code "73") (name "unconnected-(IC3A-Y8-Pad11)") (class "Default")
      (node (ref "IC3") (pin "11") (pinfunction "Y8_11") (pintype "tri_state"))
    )
    (net (code "74") (name "unconnected-(IC4A-G1-Pad1)") (class "Default")
      (node (ref "IC4") (pin "1") (pinfunction "G1_1") (pintype "input"))
    )
    (net (code "75") (name "unconnected-(IC4A-G2-Pad19)") (class "Default")
      (node (ref "IC4") (pin "19") (pinfunction "G2_19") (pintype "input"))
    )
    (net (code "76") (name "unconnected-(IC6A-I-Pad1)") (class "Default")
      (node (ref "IC6") (pin "1") (pinfunction "I_1") (pintype "input"))
    )
    (net (code "77") (name "unconnected-(IC6A-O-Pad2)") (class "Default")
      (node (ref "IC6") (pin "2") (pinfunction "O_2") (pintype "open_collector"))
    )
    (net (code "78") (name "unconnected-(IC6B-I-Pad3)") (class "Default")
      (node (ref "IC6") (pin "3") (pinfunction "I_3") (pintype "input"))
    )
    (net (code "79") (name "unconnected-(IC6B-O-Pad4)") (class "Default")
      (node (ref "IC6") (pin "4") (pinfunction "O_4") (pintype "open_collector"))
    )
    (net (code "80") (name "unconnected-(IC6C-I-Pad5)") (class "Default")
      (node (ref "IC6") (pin "5") (pinfunction "I_5") (pintype "input"))
    )
    (net (code "81") (name "unconnected-(IC6C-O-Pad6)") (class "Default")
      (node (ref "IC6") (pin "6") (pinfunction "O_6") (pintype "open_collector"))
    )
    (net (code "82") (name "unconnected-(IC6D-I-Pad9)") (class "Default")
      (node (ref "IC6") (pin "9") (pinfunction "I_9") (pintype "input"))
    )
    (net (code "83") (name "unconnected-(IC6D-O-Pad8)") (class "Default")
      (node (ref "IC6") (pin "8") (pinfunction "O_8") (pintype "open_collector"))
    )
    (net (code "84") (name "unconnected-(IC6E-I-Pad11)") (class "Default")
      (node (ref "IC6") (pin "11") (pinfunction "I_11") (pintype "input"))
    )
    (net (code "85") (name "unconnected-(IC6E-O-Pad10)") (class "Default")
      (node (ref "IC6") (pin "10") (pinfunction "O_10") (pintype "open_collector"))
    )
    (net (code "86") (name "unconnected-(IC6F-I-Pad13)") (class "Default")
      (node (ref "IC6") (pin "13") (pinfunction "I_13") (pintype "input"))
    )
    (net (code "87") (name "unconnected-(IC6F-O-Pad12)") (class "Default")
      (node (ref "IC6") (pin "12") (pinfunction "O_12") (pintype "open_collector"))
    )
    (net (code "88") (name "unconnected-(SV1-Pad1)") (class "Default")
      (node (ref "SV1") (pin "1") (pinfunction "1_1") (pintype "passive"))
    )
    (net (code "89") (name "unconnected-(SV1-Pad2)") (class "Default")
      (node (ref "SV1") (pin "2") (pinfunction "2_2") (pintype "passive"))
    )
    (net (code "90") (name "unconnected-(SV1-Pad3)") (class "Default")
      (node (ref "SV1") (pin "3") (pinfunction "3_3") (pintype "passive"))
    )
    (net (code "91") (name "unconnected-(SV1-Pad4)") (class "Default")
      (node (ref "SV1") (pin "4") (pinfunction "4_4") (pintype "passive"))
    )
    (net (code "92") (name "unconnected-(SV1-Pad5)") (class "Default")
      (node (ref "SV1") (pin "5") (pinfunction "5_5") (pintype "passive"))
    )
    (net (code "93") (name "unconnected-(SV1-Pad6)") (class "Default")
      (node (ref "SV1") (pin "6") (pinfunction "6_6") (pintype "passive"))
    )
    (net (code "94") (name "unconnected-(SV2-Pad1)") (class "Default")
      (node (ref "SV2") (pin "1") (pinfunction "1_1") (pintype "passive"))
    )
    (net (code "95") (name "unconnected-(SV2-Pad2)") (class "Default")
      (node (ref "SV2") (pin "2") (pinfunction "2_2") (pintype "passive"))
    )
    (net (code "96") (name "unconnected-(SV2-Pad3)") (class "Default")
      (node (ref "SV2") (pin "3") (pinfunction "3_3") (pintype "passive"))
    )
    (net (code "97") (name "unconnected-(SV2-Pad4)") (class "Default")
      (node (ref "SV2") (pin "4") (pinfunction "4_4") (pintype "passive"))
    )
    (net (code "98") (name "unconnected-(SV2-Pad8)") (class "Default")
      (node (ref "SV2") (pin "8") (pinfunction "8_8") (pintype "passive"))
    )
    (net (code "99") (name "unconnected-(SV5-Pad5)") (class "Default")
      (node (ref "SV5") (pin "5") (pinfunction "5_5") (pintype "passive"))
    )
    (net (code "100") (name "unconnected-(SV7-Pad5)") (class "Default")
      (node (ref "SV7") (pin "5") (pinfunction "5_5") (pintype "passive"))
    )
    (net (code "101") (name "unconnected-(SV7-Pad7)") (class "Default")
      (node (ref "SV7") (pin "7") (pinfunction "7_7") (pintype "passive"))
    )
    (net (code "102") (name "unconnected-(SV7-Pad9)") (class "Default")
      (node (ref "SV7") (pin "9") (pinfunction "9_9") (pintype "passive"))
    )
    (net (code "103") (name "unconnected-(SV7-Pad10)") (class "Default")
      (node (ref "SV7") (pin "10") (pinfunction "10_10") (pintype "passive"))
    )
    (net (code "104") (name "unconnected-(SV7-Pad11)") (class "Default")
      (node (ref "SV7") (pin "11") (pinfunction "11_11") (pintype "passive"))
    )
    (net (code "105") (name "unconnected-(SV7-Pad12)") (class "Default")
      (node (ref "SV7") (pin "12") (pinfunction "12_12") (pintype "passive"))
    )
    (net (code "106") (name "unconnected-(SV7-Pad13)") (class "Default")
      (node (ref "SV7") (pin "13") (pinfunction "13_13") (pintype "passive"))
    )
    (net (code "107") (name "unconnected-(SV7-Pad14)") (class "Default")
      (node (ref "SV7") (pin "14") (pinfunction "14_14") (pintype "passive"))
    )
    (net (code "108") (name "unconnected-(SV7-Pad15)") (class "Default")
      (node (ref "SV7") (pin "15") (pinfunction "15_15") (pintype "passive"))
    )
    (net (code "109") (name "unconnected-(SV7-Pad16)") (class "Default")
      (node (ref "SV7") (pin "16") (pinfunction "16_16") (pintype "passive"))
    )
    (net (code "110") (name "unconnected-(SV7-Pad17)") (class "Default")
      (node (ref "SV7") (pin "17") (pinfunction "17_17") (pintype "passive"))
    )
    (net (code "111") (name "unconnected-(SV7-Pad18)") (class "Default")
      (node (ref "SV7") (pin "18") (pinfunction "18_18") (pintype "passive"))
    )
    (net (code "112") (name "unconnected-(SV7-Pad19)") (class "Default")
      (node (ref "SV7") (pin "19") (pinfunction "19_19") (pintype "passive"))
    )
    (net (code "113") (name "unconnected-(SV7-Pad20)") (class "Default")
      (node (ref "SV7") (pin "20") (pinfunction "20_20") (pintype "passive"))
    )
  )
)
